# controller.net
KiCad netlist of a schematic drawn in EAGLE
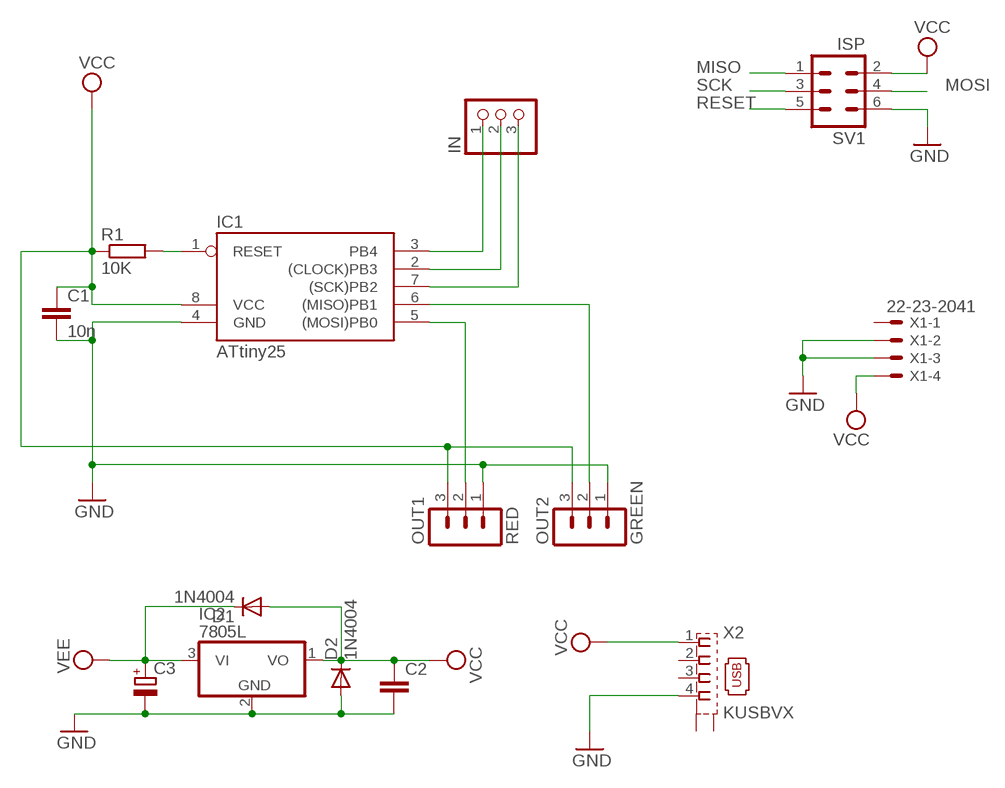
[diagram p0: schematic, sheet 1]

(export (version "E")
  (design (tool "Eeschema 10.0.6"))
  (components
    (comp (ref "C1")
      (value "10n")
      (footprint "eagle-import:C025-024X044")
      (libsource (lib "eagle-import") (part "C-EU025-024X044"))
    )
    (comp (ref "C2")
      (value "C-EU025-024X044")
      (footprint "eagle-import:C025-024X044")
      (libsource (lib "eagle-import") (part "C-EU025-024X044"))
    )
    (comp (ref "C3")
      (value "CPOL-EUE5-4")
      (footprint "eagle-import:E5-4")
      (libsource (lib "eagle-import") (part "CPOL-EUE5-4"))
    )
    (comp (ref "D1")
      (value "1N4004")
      (footprint "eagle-import:DO41-10")
      (libsource (lib "eagle-import") (part "1N4004"))
    )
    (comp (ref "D2")
      (value "1N4004")
      (footprint "eagle-import:DO41-10")
      (libsource (lib "eagle-import") (part "1N4004"))
    )
    (comp (ref "IC1")
      (value "ATtiny25")
      (footprint "eagle-import:DIL08")
      (libsource (lib "eagle-import") (part "AT902343PS"))
    )
    (comp (ref "IC2")
      (value "7805L")
      (footprint "eagle-import:TO92")
      (libsource (lib "eagle-import") (part "78L05"))
    )
    (comp (ref "IN")
      (value "PINHD-1X3/90")
      (footprint "eagle-import:1X03_90")
      (libsource (lib "eagle-import") (part "PINHD-1X3/90"))
    )
    (comp (ref "OUT1")
      (value "RED")
      (footprint "eagle-import:MA03-1")
      (libsource (lib "eagle-import") (part "MA03-1"))
    )
    (comp (ref "OUT2")
      (value "GREEN")
      (footprint "eagle-import:MA03-1")
      (libsource (lib "eagle-import") (part "MA03-1"))
    )
    (comp (ref "R1")
      (value "10K")
      (footprint "eagle-import:0207_10")
      (libsource (lib "eagle-import") (part "R-EU_0207/10"))
    )
    (comp (ref "SV1")
      (value "ISP")
      (footprint "eagle-import:MA03-2")
      (libsource (lib "eagle-import") (part "MA03-2"))
    )
    (comp (ref "X1")
      (value "22-23-2041")
      (footprint "eagle-import:22-23-2041")
      (fields (field (name "MF") "MOLEX"))
      (libsource (lib "eagle-import") (part "22-23-2041"))
    )
    (comp (ref "X2")
      (value "KUSBVX")
      (footprint "eagle-import:KUSBVX")
      (libsource (lib "eagle-import") (part "KUSBVX"))
    )
  )
  (nets
    (net (code "1") (name "/MISO") (class "Default")
      (node (ref "IC1") (pin "6") (pinfunction "(MISO)PB1_6") (pintype "bidirectional"))
      (node (ref "OUT2") (pin "2") (pinfunction "2_2") (pintype "passive"))
      (node (ref "SV1") (pin "1") (pinfunction "1_1") (pintype "passive"))
    )
    (net (code "2") (name "/MOSI") (class "Default")
      (node (ref "IC1") (pin "5") (pinfunction "(MOSI)PB0_5") (pintype "bidirectional"))
      (node (ref "OUT1") (pin "2") (pinfunction "2_2") (pintype "passive"))
      (node (ref "SV1") (pin "4") (pinfunction "4_4") (pintype "passive"))
    )
    (net (code "3") (name "/RESET") (class "Default")
      (node (ref "IC1") (pin "1") (pinfunction "RESET_1") (pintype "input"))
      (node (ref "R1") (pin "2") (pinfunction "2_2") (pintype "passive"))
      (node (ref "SV1") (pin "5") (pinfunction "5_5") (pintype "passive"))
    )
    (net (code "4") (name "/SCK") (class "Default")
      (node (ref "IC1") (pin "7") (pinfunction "(SCK)PB2_7") (pintype "bidirectional"))
      (node (ref "IN") (pin "3") (pinfunction "3_3") (pintype "passive"))
      (node (ref "SV1") (pin "3") (pinfunction "3_3") (pintype "passive"))
    )
    (net (code "5") (name "GND") (class "Default")
      (node (ref "C1") (pin "2") (pinfunction "2_2") (pintype "passive"))
      (node (ref "C2") (pin "2") (pinfunction "2_2") (pintype "passive"))
      (node (ref "C3") (pin "-") (pinfunction "-_-") (pintype "passive"))
      (node (ref "D2") (pin "A") (pinfunction "A_A") (pintype "passive"))
      (node (ref "IC1") (pin "4") (pinfunction "GND_4") (pintype "power_in"))
      (node (ref "IC2") (pin "2") (pinfunction "GND_2") (pintype "passive"))
      (node (ref "OUT1") (pin "1") (pinfunction "1_1") (pintype "passive"))
      (node (ref "OUT2") (pin "1") (pinfunction "1_1") (pintype "passive"))
      (node (ref "SV1") (pin "6") (pinfunction "6_6") (pintype "passive"))
      (node (ref "X1") (pin "2") (pinfunction "S_2") (pintype "passive"))
      (node (ref "X1") (pin "3") (pinfunction "S_3") (pintype "passive"))
      (node (ref "X2") (pin "4") (pinfunction "4_4") (pintype "passive"))
    )
    (net (code "6") (name "Net-(IC1-(CLOCK)PB3)") (class "Default")
      (node (ref "IC1") (pin "2") (pinfunction "(CLOCK)PB3_2") (pintype "bidirectional"))
      (node (ref "IN") (pin "2") (pinfunction "2_2") (pintype "passive"))
    )
    (net (code "7") (name "Net-(IC1-PB4)") (class "Default")
      (node (ref "IC1") (pin "3") (pinfunction "PB4_3") (pintype "bidirectional"))
      (node (ref "IN") (pin "1") (pinfunction "1_1") (pintype "passive"))
    )
    (net (code "8") (name "VCC") (class "Default")
      (node (ref "C1") (pin "1") (pinfunction "1_1") (pintype "passive"))
      (node (ref "C2") (pin "1") (pinfunction "1_1") (pintype "passive"))
      (node (ref "D1") (pin "A") (pinfunction "A_A") (pintype "passive"))
      (node (ref "D2") (pin "C") (pinfunction "C_C") (pintype "passive"))
      (node (ref "IC1") (pin "8") (pinfunction "VCC_8") (pintype "power_in"))
      (node (ref "IC2") (pin "1") (pinfunction "VO_1") (pintype "passive"))
      (node (ref "OUT1") (pin "3") (pinfunction "3_3") (pintype "passive"))
      (node (ref "OUT2") (pin "3") (pinfunction "3_3") (pintype "passive"))
      (node (ref "R1") (pin "1") (pinfunction "1_1") (pintype "passive"))
      (node (ref "SV1") (pin "2") (pinfunction "2_2") (pintype "passive"))
      (node (ref "X1") (pin "4") (pinfunction "S_4") (pintype "passive"))
      (node (ref "X2") (pin "1") (pinfunction "1_1") (pintype "passive"))
    )
    (net (code "9") (name "VEE") (class "Default")
      (node (ref "C3") (pin "+") (pinfunction "+_+") (pintype "passive"))
      (node (ref "D1") (pin "C") (pinfunction "C_C") (pintype "passive"))
      (node (ref "IC2") (pin "3") (pinfunction "VI_3") (pintype "input"))
    )
    (net (code "10") (name "unconnected-(X1A-S-Pad1)") (class "Default")
      (node (ref "X1") (pin "1") (pinfunction "S_1") (pintype "passive"))
    )
    (net (code "11") (name "unconnected-(X2-Pad2)") (class "Default")
      (node (ref "X2") (pin "2") (pinfunction "2_2") (pintype "passive"))
    )
    (net (code "12") (name "unconnected-(X2-Pad3)") (class "Default")
      (node (ref "X2") (pin "3") (pinfunction "3_3") (pintype "passive"))
    )
    (net (code "13") (name "unconnected-(X2-S1-PadM1)") (class "Default")
      (node (ref "X2") (pin "M1") (pinfunction "S1_M1") (pintype "passive"))
    )
    (net (code "14") (name "unconnected-(X2-S2-PadM2)") (class "Default")
      (node (ref "X2") (pin "M2") (pinfunction "S2_M2") (pintype "passive"))
    )
  )
)
